# ArduinoNano7segSCH.net
KiCad netlist of a schematic drawn in Altium Designer
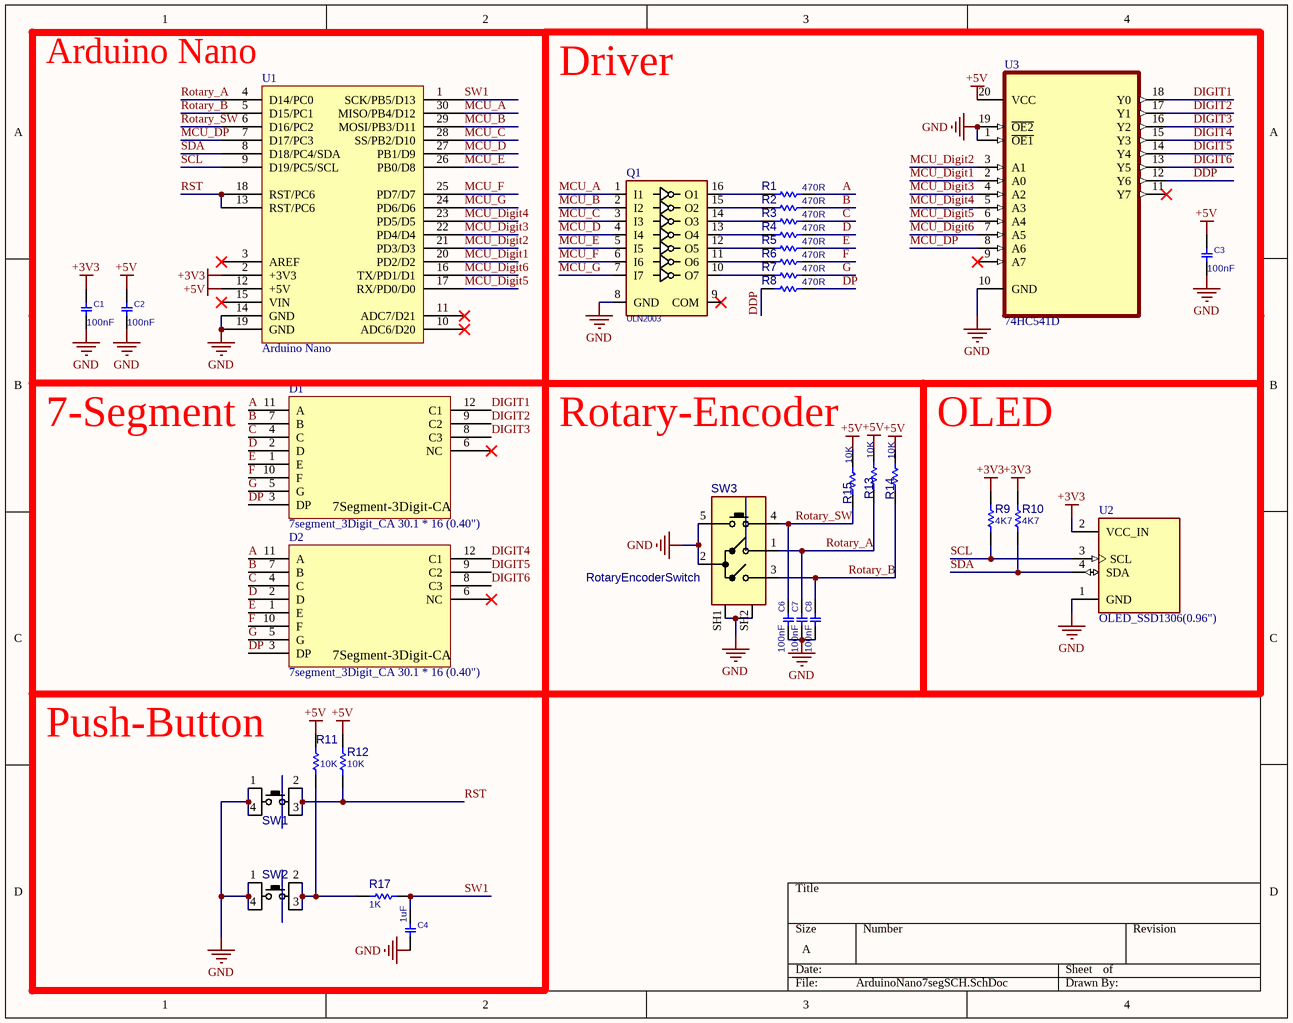
[diagram p0: ArduinoNano7segSCH.SchDoc]

(export (version "E")
  (design (tool "Eeschema 10.0.6"))
  (components
    (comp (ref "C1")
      (value "100nF")
      (footprint "C0805")
      (description "CAP, MLCC")
      (fields (field (name "MANF_P#") "MANF_PART#"))
      (libsource (lib "passive_smd") (part "CAP_SMD_MLCC_0805"))
    )
    (comp (ref "C2")
      (value "100nF")
      (footprint "C0805")
      (description "CAP, MLCC")
      (fields (field (name "MANF_P#") "MANF_PART#"))
      (libsource (lib "passive_smd") (part "CAP_SMD_MLCC_0805"))
    )
    (comp (ref "C3")
      (value "100nF")
      (footprint "C0805")
      (description "CAP, MLCC")
      (fields (field (name "MANF_P#") "MANF_PART#"))
      (libsource (lib "passive_smd") (part "CAP_SMD_MLCC_0805"))
    )
    (comp (ref "C4")
      (value "1uF")
      (footprint "C0805")
      (description "CAP, MLCC")
      (fields (field (name "MANF_P#") "MANF_PART#"))
      (libsource (lib "passive_smd") (part "CAP_SMD_MLCC_0805"))
    )
    (comp (ref "C6")
      (value "100nF")
      (footprint "C0805")
      (description "CAP, MLCC")
      (fields (field (name "MANF_P#") "MANF_PART#"))
      (libsource (lib "passive_smd") (part "CAP_SMD_MLCC_0805"))
    )
    (comp (ref "C7")
      (value "100nF")
      (footprint "C0805")
      (description "CAP, MLCC")
      (fields (field (name "MANF_P#") "MANF_PART#"))
      (libsource (lib "passive_smd") (part "CAP_SMD_MLCC_0805"))
    )
    (comp (ref "C8")
      (value "100nF")
      (footprint "C0805")
      (description "CAP, MLCC")
      (fields (field (name "MANF_P#") "MANF_PART#"))
      (libsource (lib "passive_smd") (part "CAP_SMD_MLCC_0805"))
    )
    (comp (ref "D1")
      (value "7segment_3Digit_CA 30.1 * 16 (0.40\")")
      (footprint "7Seg3Digit")
      (libsource (lib "Mehrdad") (part "7segment_3Digit_CA"))
    )
    (comp (ref "D2")
      (value "7segment_3Digit_CA 30.1 * 16 (0.40\")")
      (footprint "7Seg3Digit")
      (libsource (lib "Mehrdad") (part "7segment_3Digit_CA"))
    )
    (comp (ref "Q1")
      (value "ULN2003")
      (footprint "SO_16")
      (description "Darlington, 7-CH, 50V, 0.5A, 5V TTL/CMOS")
      (fields (field (name "MANF_P#") "ULN2003D1") (field (name "MANF") "ST"))
      (libsource (lib "transistor_bjt") (part "ULN2003_SOP16_ST"))
    )
    (comp (ref "R1")
      (value "470R")
      (footprint "R0805")
      (description "RESISTOR, SMD")
      (libsource (lib "passive_smd") (part "RES_SMD_0805"))
    )
    (comp (ref "R2")
      (value "470R")
      (footprint "R0805")
      (description "RESISTOR, SMD")
      (libsource (lib "passive_smd") (part "RES_SMD_0805"))
    )
    (comp (ref "R3")
      (value "470R")
      (footprint "R0805")
      (description "RESISTOR, SMD")
      (libsource (lib "passive_smd") (part "RES_SMD_0805"))
    )
    (comp (ref "R4")
      (value "470R")
      (footprint "R0805")
      (description "RESISTOR, SMD")
      (libsource (lib "passive_smd") (part "RES_SMD_0805"))
    )
    (comp (ref "R5")
      (value "470R")
      (footprint "R0805")
      (description "RESISTOR, SMD")
      (libsource (lib "passive_smd") (part "RES_SMD_0805"))
    )
    (comp (ref "R6")
      (value "470R")
      (footprint "R0805")
      (description "RESISTOR, SMD")
      (libsource (lib "passive_smd") (part "RES_SMD_0805"))
    )
    (comp (ref "R7")
      (value "470R")
      (footprint "R0805")
      (description "RESISTOR, SMD")
      (libsource (lib "passive_smd") (part "RES_SMD_0805"))
    )
    (comp (ref "R8")
      (value "470R")
      (footprint "R0805")
      (description "RESISTOR, SMD")
      (libsource (lib "passive_smd") (part "RES_SMD_0805"))
    )
    (comp (ref "R9")
      (value "4K7")
      (footprint "R0805")
      (description "RESISTOR, SMD")
      (libsource (lib "passive_smd") (part "RES_SMD_0805"))
    )
    (comp (ref "R10")
      (value "4K7")
      (footprint "R0805")
      (description "RESISTOR, SMD")
      (libsource (lib "passive_smd") (part "RES_SMD_0805"))
    )
    (comp (ref "R11")
      (value "10K")
      (footprint "R0805")
      (description "RESISTOR, SMD")
      (libsource (lib "passive_smd") (part "RES_SMD_0805"))
    )
    (comp (ref "R12")
      (value "10K")
      (footprint "R0805")
      (description "RESISTOR, SMD")
      (libsource (lib "passive_smd") (part "RES_SMD_0805"))
    )
    (comp (ref "R13")
      (value "10K")
      (footprint "R0805")
      (description "RESISTOR, SMD")
      (libsource (lib "passive_smd") (part "RES_SMD_0805"))
    )
    (comp (ref "R14")
      (value "10K")
      (footprint "R0805")
      (description "RESISTOR, SMD")
      (libsource (lib "passive_smd") (part "RES_SMD_0805"))
    )
    (comp (ref "R15")
      (value "10K")
      (footprint "R0805")
      (description "RESISTOR, SMD")
      (libsource (lib "passive_smd") (part "RES_SMD_0805"))
    )
    (comp (ref "R17")
      (value "1K")
      (footprint "R0805")
      (description "RESISTOR, SMD")
      (libsource (lib "passive_smd") (part "RES_SMD_0805"))
    )
    (comp (ref "SW1")
      (value "PUSHBUTTON")
      (footprint "SWPBS_SPDT_6X6X4")
      (description "SWITCH, PUSH BUTTON, TACTILE, SMD, SPDT, 6X6X4.3mm")
      (fields (field (name "MANF") "Bond-Tact") (field (name "MANF_P#") "TS-1143S"))
      (libsource (lib "switch_tact_PUSHB") (part "SWPBS_SPDT_6X6X4"))
    )
    (comp (ref "SW2")
      (value "PUSHBUTTON")
      (footprint "SWPBT_SPDT_12X12SKHC")
      (description "SWITCH, PUSH BUTTON, TACTILE, THD, SPDT, 12X12X7.3mm")
      (fields (field (name "MANF") "ALPS") (field (name "MANF_P#") "SKHCBEA010"))
      (libsource (lib "switch_tact_PUSHB") (part "SWPBT_SPDT_12X12_SKHCBEA010"))
    )
    (comp (ref "SW3")
      (value "RotaryEncoderSwitch")
      (footprint "SWROT_11MM")
      (description "SWITCH, ROTARY Encoder, 11mm Metal Shaft")
      (fields (field (name "MANF") "Alpha") (field (name "MANF_PART#") "RE111F-41B3N-15F-20P"))
      (libsource (lib "switch_rotary_encoder") (part "SWROT_11MM"))
    )
    (comp (ref "U1")
      (value "Arduino Nano")
      (footprint "Arduino Nano")
      (libsource (lib "Mehrdad") (part "Arduino Nano"))
    )
    (comp (ref "U2")
      (value "OLED_SSD1306(0.96\")")
      (footprint "OLED_Display 0.96\" 64*128")
      (libsource (lib "Mehrdad") (part "OLED_Display 0.96{dblquote} 64*128"))
    )
    (comp (ref "U3")
      (value "74HC541D")
      (footprint "74HC541D")
      (description "Buffer, Non-Inverting 1 Element 8 Bit per Element 3-State Output 20-SOIC")
      (libsource (lib "Mehrdad") (part "74HC541D"))
    )
  )
  (nets
    (net (code "1") (name "+3V3") (class "Default")
      (node (ref "C1") (pin "2") (pinfunction "2_2") (pintype "passive"))
      (node (ref "R10") (pin "2") (pinfunction "2_2") (pintype "passive"))
      (node (ref "R9") (pin "2") (pinfunction "2_2") (pintype "passive"))
      (node (ref "U1") (pin "2") (pinfunction "+3V3_2") (pintype "passive"))
      (node (ref "U2") (pin "2") (pinfunction "VCC_IN_2") (pintype "power_in"))
    )
    (net (code "2") (name "+5V") (class "Default")
      (node (ref "C2") (pin "2") (pinfunction "2_2") (pintype "passive"))
      (node (ref "C3") (pin "2") (pinfunction "2_2") (pintype "passive"))
      (node (ref "R11") (pin "2") (pinfunction "2_2") (pintype "passive"))
      (node (ref "R12") (pin "2") (pinfunction "2_2") (pintype "passive"))
      (node (ref "R13") (pin "2") (pinfunction "2_2") (pintype "passive"))
      (node (ref "R14") (pin "2") (pinfunction "2_2") (pintype "passive"))
      (node (ref "R15") (pin "2") (pinfunction "2_2") (pintype "passive"))
      (node (ref "U1") (pin "12") (pinfunction "+5V_12") (pintype "passive"))
      (node (ref "U3") (pin "20") (pinfunction "VCC_20") (pintype "power_in"))
    )
    (net (code "3") (name "/A") (class "Default")
      (node (ref "D1") (pin "11") (pinfunction "A_11") (pintype "passive"))
      (node (ref "D2") (pin "11") (pinfunction "A_11") (pintype "passive"))
      (node (ref "R1") (pin "1") (pinfunction "1_1") (pintype "passive"))
    )
    (net (code "4") (name "/B") (class "Default")
      (node (ref "D1") (pin "7") (pinfunction "B_7") (pintype "passive"))
      (node (ref "D2") (pin "7") (pinfunction "B_7") (pintype "passive"))
      (node (ref "R2") (pin "1") (pinfunction "1_1") (pintype "passive"))
    )
    (net (code "5") (name "/C") (class "Default")
      (node (ref "D1") (pin "4") (pinfunction "C_4") (pintype "passive"))
      (node (ref "D2") (pin "4") (pinfunction "C_4") (pintype "passive"))
      (node (ref "R3") (pin "1") (pinfunction "1_1") (pintype "passive"))
    )
    (net (code "6") (name "/D") (class "Default")
      (node (ref "D1") (pin "2") (pinfunction "D_2") (pintype "passive"))
      (node (ref "D2") (pin "2") (pinfunction "D_2") (pintype "passive"))
      (node (ref "R4") (pin "1") (pinfunction "1_1") (pintype "passive"))
    )
    (net (code "7") (name "/DDP") (class "Default")
      (node (ref "R8") (pin "2") (pinfunction "2_2") (pintype "passive"))
      (node (ref "U3") (pin "12") (pinfunction "Y6_12") (pintype "output"))
    )
    (net (code "8") (name "/DIGIT1") (class "Default")
      (node (ref "D1") (pin "12") (pinfunction "C1_12") (pintype "passive"))
      (node (ref "U3") (pin "18") (pinfunction "Y0_18") (pintype "output"))
    )
    (net (code "9") (name "/DIGIT2") (class "Default")
      (node (ref "D1") (pin "9") (pinfunction "C2_9") (pintype "passive"))
      (node (ref "U3") (pin "17") (pinfunction "Y1_17") (pintype "output"))
    )
    (net (code "10") (name "/DIGIT3") (class "Default")
      (node (ref "D1") (pin "8") (pinfunction "C3_8") (pintype "passive"))
      (node (ref "U3") (pin "16") (pinfunction "Y2_16") (pintype "output"))
    )
    (net (code "11") (name "/DIGIT4") (class "Default")
      (node (ref "D2") (pin "12") (pinfunction "C1_12") (pintype "passive"))
      (node (ref "U3") (pin "15") (pinfunction "Y3_15") (pintype "output"))
    )
    (net (code "12") (name "/DIGIT5") (class "Default")
      (node (ref "D2") (pin "9") (pinfunction "C2_9") (pintype "passive"))
      (node (ref "U3") (pin "14") (pinfunction "Y4_14") (pintype "output"))
    )
    (net (code "13") (name "/DIGIT6") (class "Default")
      (node (ref "D2") (pin "8") (pinfunction "C3_8") (pintype "passive"))
      (node (ref "U3") (pin "13") (pinfunction "Y5_13") (pintype "output"))
    )
    (net (code "14") (name "/DP") (class "Default")
      (node (ref "D1") (pin "3") (pinfunction "DP_3") (pintype "passive"))
      (node (ref "D2") (pin "3") (pinfunction "DP_3") (pintype "passive"))
      (node (ref "R8") (pin "1") (pinfunction "1_1") (pintype "passive"))
    )
    (net (code "15") (name "/E") (class "Default")
      (node (ref "D1") (pin "1") (pinfunction "E_1") (pintype "passive"))
      (node (ref "D2") (pin "1") (pinfunction "E_1") (pintype "passive"))
      (node (ref "R5") (pin "1") (pinfunction "1_1") (pintype "passive"))
    )
    (net (code "16") (name "/F") (class "Default")
      (node (ref "D1") (pin "10") (pinfunction "F_10") (pintype "passive"))
      (node (ref "D2") (pin "10") (pinfunction "F_10") (pintype "passive"))
      (node (ref "R6") (pin "1") (pinfunction "1_1") (pintype "passive"))
    )
    (net (code "17") (name "/G") (class "Default")
      (node (ref "D1") (pin "5") (pinfunction "G_5") (pintype "passive"))
      (node (ref "D2") (pin "5") (pinfunction "G_5") (pintype "passive"))
      (node (ref "R7") (pin "1") (pinfunction "1_1") (pintype "passive"))
    )
    (net (code "18") (name "/MCU_A") (class "Default")
      (node (ref "Q1") (pin "1") (pinfunction "I1_1") (pintype "passive"))
      (node (ref "U1") (pin "30") (pinfunction "MISO/PB4/D12_30") (pintype "passive"))
    )
    (net (code "19") (name "/MCU_B") (class "Default")
      (node (ref "Q1") (pin "2") (pinfunction "I2_2") (pintype "passive"))
      (node (ref "U1") (pin "29") (pinfunction "MOSI/PB3/D11_29") (pintype "passive"))
    )
    (net (code "20") (name "/MCU_C") (class "Default")
      (node (ref "Q1") (pin "3") (pinfunction "I3_3") (pintype "passive"))
      (node (ref "U1") (pin "28") (pinfunction "SS/PB2/D10_28") (pintype "passive"))
    )
    (net (code "21") (name "/MCU_D") (class "Default")
      (node (ref "Q1") (pin "4") (pinfunction "I4_4") (pintype "passive"))
      (node (ref "U1") (pin "27") (pinfunction "PB1/D9_27") (pintype "passive"))
    )
    (net (code "22") (name "/MCU_DP") (class "Default")
      (node (ref "U1") (pin "7") (pinfunction "D17/PC3_7") (pintype "passive"))
      (node (ref "U3") (pin "8") (pinfunction "A6_8") (pintype "input"))
    )
    (net (code "23") (name "/MCU_Digit1") (class "Default")
      (node (ref "U1") (pin "20") (pinfunction "PD2/D2_20") (pintype "passive"))
      (node (ref "U3") (pin "2") (pinfunction "A0_2") (pintype "input"))
    )
    (net (code "24") (name "/MCU_Digit2") (class "Default")
      (node (ref "U1") (pin "21") (pinfunction "PD3/D3_21") (pintype "passive"))
      (node (ref "U3") (pin "3") (pinfunction "A1_3") (pintype "input"))
    )
    (net (code "25") (name "/MCU_Digit3") (class "Default")
      (node (ref "U1") (pin "22") (pinfunction "PD4/D4_22") (pintype "passive"))
      (node (ref "U3") (pin "4") (pinfunction "A2_4") (pintype "input"))
    )
    (net (code "26") (name "/MCU_Digit4") (class "Default")
      (node (ref "U1") (pin "23") (pinfunction "PD5/D5_23") (pintype "passive"))
      (node (ref "U3") (pin "5") (pinfunction "A3_5") (pintype "input"))
    )
    (net (code "27") (name "/MCU_Digit5") (class "Default")
      (node (ref "U1") (pin "17") (pinfunction "RX/PD0/D0_17") (pintype "passive"))
      (node (ref "U3") (pin "6") (pinfunction "A4_6") (pintype "input"))
    )
    (net (code "28") (name "/MCU_Digit6") (class "Default")
      (node (ref "U1") (pin "16") (pinfunction "TX/PD1/D1_16") (pintype "passive"))
      (node (ref "U3") (pin "7") (pinfunction "A5_7") (pintype "input"))
    )
    (net (code "29") (name "/MCU_E") (class "Default")
      (node (ref "Q1") (pin "5") (pinfunction "I5_5") (pintype "passive"))
      (node (ref "U1") (pin "26") (pinfunction "PB0/D8_26") (pintype "passive"))
    )
    (net (code "30") (name "/MCU_F") (class "Default")
      (node (ref "Q1") (pin "6") (pinfunction "I6_6") (pintype "passive"))
      (node (ref "U1") (pin "25") (pinfunction "PD7/D7_25") (pintype "passive"))
    )
    (net (code "31") (name "/MCU_G") (class "Default")
      (node (ref "Q1") (pin "7") (pinfunction "I7_7") (pintype "passive"))
      (node (ref "U1") (pin "24") (pinfunction "PD6/D6_24") (pintype "passive"))
    )
    (net (code "32") (name "/RST") (class "Default")
      (node (ref "R12") (pin "1") (pinfunction "1_1") (pintype "passive"))
      (node (ref "SW1") (pin "2") (pinfunction "P3_2") (pintype "passive"))
      (node (ref "SW1") (pin "3") (pinfunction "P4_3") (pintype "passive"))
      (node (ref "U1") (pin "13") (pinfunction "RST/PC6_13") (pintype "passive"))
      (node (ref "U1") (pin "18") (pinfunction "RST/PC6_18") (pintype "passive"))
    )
    (net (code "33") (name "/Rotary_A") (class "Default")
      (node (ref "C7") (pin "2") (pinfunction "2_2") (pintype "passive"))
      (node (ref "R13") (pin "1") (pinfunction "1_1") (pintype "passive"))
      (node (ref "SW3") (pin "1") (pinfunction "A_1") (pintype "passive"))
      (node (ref "U1") (pin "4") (pinfunction "D14/PC0_4") (pintype "passive"))
    )
    (net (code "34") (name "/Rotary_B") (class "Default")
      (node (ref "C8") (pin "2") (pinfunction "2_2") (pintype "passive"))
      (node (ref "R14") (pin "1") (pinfunction "1_1") (pintype "passive"))
      (node (ref "SW3") (pin "3") (pinfunction "B_3") (pintype "passive"))
      (node (ref "U1") (pin "5") (pinfunction "D15/PC1_5") (pintype "passive"))
    )
    (net (code "35") (name "/Rotary_SW") (class "Default")
      (node (ref "C6") (pin "2") (pinfunction "2_2") (pintype "passive"))
      (node (ref "R15") (pin "1") (pinfunction "1_1") (pintype "passive"))
      (node (ref "SW3") (pin "4") (pinfunction "E_4") (pintype "passive"))
      (node (ref "U1") (pin "6") (pinfunction "D16/PC2_6") (pintype "passive"))
    )
    (net (code "36") (name "/SCL") (class "Default")
      (node (ref "R9") (pin "1") (pinfunction "1_1") (pintype "passive"))
      (node (ref "U1") (pin "9") (pinfunction "D19/PC5/SCL_9") (pintype "passive"))
      (node (ref "U2") (pin "3") (pinfunction "SCL_3") (pintype "input"))
    )
    (net (code "37") (name "/SDA") (class "Default")
      (node (ref "R10") (pin "1") (pinfunction "1_1") (pintype "passive"))
      (node (ref "U1") (pin "8") (pinfunction "D18/PC4/SDA_8") (pintype "passive"))
      (node (ref "U2") (pin "4") (pinfunction "SDA_4") (pintype "bidirectional"))
    )
    (net (code "38") (name "/SW1") (class "Default")
      (node (ref "C4") (pin "2") (pinfunction "2_2") (pintype "passive"))
      (node (ref "R17") (pin "1") (pinfunction "1_1") (pintype "passive"))
      (node (ref "U1") (pin "1") (pinfunction "SCK/PB5/D13_1") (pintype "passive"))
    )
    (net (code "39") (name "GND") (class "Default")
      (node (ref "C1") (pin "1") (pinfunction "1_1") (pintype "passive"))
      (node (ref "C2") (pin "1") (pinfunction "1_1") (pintype "passive"))
      (node (ref "C3") (pin "1") (pinfunction "1_1") (pintype "passive"))
      (node (ref "C4") (pin "1") (pinfunction "1_1") (pintype "passive"))
      (node (ref "C6") (pin "1") (pinfunction "1_1") (pintype "passive"))
      (node (ref "C7") (pin "1") (pinfunction "1_1") (pintype "passive"))
      (node (ref "C8") (pin "1") (pinfunction "1_1") (pintype "passive"))
      (node (ref "Q1") (pin "8") (pinfunction "GND_8") (pintype "passive"))
      (node (ref "SW1") (pin "1") (pinfunction "P1_1") (pintype "passive"))
      (node (ref "SW1") (pin "4") (pinfunction "P2_4") (pintype "passive"))
      (node (ref "SW2") (pin "1") (pinfunction "P1_1") (pintype "passive"))
      (node (ref "SW2") (pin "4") (pinfunction "P2_4") (pintype "passive"))
      (node (ref "SW3") (pin "2") (pinfunction "C_2") (pintype "passive"))
      (node (ref "SW3") (pin "5") (pinfunction "D_5") (pintype "passive"))
      (node (ref "SW3") (pin "SH1") (pinfunction "SH1_SH1") (pintype "passive"))
      (node (ref "SW3") (pin "SH2") (pinfunction "SH2_SH2") (pintype "passive"))
      (node (ref "U1") (pin "14") (pinfunction "GND_14") (pintype "passive"))
      (node (ref "U1") (pin "19") (pinfunction "GND_19") (pintype "passive"))
      (node (ref "U2") (pin "1") (pinfunction "GND_1") (pintype "power_in"))
      (node (ref "U3") (pin "1") (pinfunction "~{OE1}_1") (pintype "input"))
      (node (ref "U3") (pin "10") (pinfunction "GND_10") (pintype "passive"))
      (node (ref "U3") (pin "19") (pinfunction "~{OE2}_19") (pintype "input"))
    )
    (net (code "40") (name "Net-(Q1-O1)") (class "Default")
      (node (ref "Q1") (pin "16") (pinfunction "O1_16") (pintype "passive"))
      (node (ref "R1") (pin "2") (pinfunction "2_2") (pintype "passive"))
    )
    (net (code "41") (name "Net-(Q1-O2)") (class "Default")
      (node (ref "Q1") (pin "15") (pinfunction "O2_15") (pintype "passive"))
      (node (ref "R2") (pin "2") (pinfunction "2_2") (pintype "passive"))
    )
    (net (code "42") (name "Net-(Q1-O3)") (class "Default")
      (node (ref "Q1") (pin "14") (pinfunction "O3_14") (pintype "passive"))
      (node (ref "R3") (pin "2") (pinfunction "2_2") (pintype "passive"))
    )
    (net (code "43") (name "Net-(Q1-O4)") (class "Default")
      (node (ref "Q1") (pin "13") (pinfunction "O4_13") (pintype "passive"))
      (node (ref "R4") (pin "2") (pinfunction "2_2") (pintype "passive"))
    )
    (net (code "44") (name "Net-(Q1-O5)") (class "Default")
      (node (ref "Q1") (pin "12") (pinfunction "O5_12") (pintype "passive"))
      (node (ref "R5") (pin "2") (pinfunction "2_2") (pintype "passive"))
    )
    (net (code "45") (name "Net-(Q1-O6)") (class "Default")
      (node (ref "Q1") (pin "11") (pinfunction "O6_11") (pintype "passive"))
      (node (ref "R6") (pin "2") (pinfunction "2_2") (pintype "passive"))
    )
    (net (code "46") (name "Net-(Q1-O7)") (class "Default")
      (node (ref "Q1") (pin "10") (pinfunction "O7_10") (pintype "passive"))
      (node (ref "R7") (pin "2") (pinfunction "2_2") (pintype "passive"))
    )
    (net (code "47") (name "Net-(SW2-P3)") (class "Default")
      (node (ref "R11") (pin "1") (pinfunction "1_1") (pintype "passive"))
      (node (ref "R17") (pin "2") (pinfunction "2_2") (pintype "passive"))
      (node (ref "SW2") (pin "2") (pinfunction "P3_2") (pintype "passive"))
      (node (ref "SW2") (pin "3") (pinfunction "P4_3") (pintype "passive"))
    )
    (net (code "48") (name "unconnected-(D1-NC-Pad6)") (class "Default")
      (node (ref "D1") (pin "6") (pinfunction "NC_6") (pintype "passive+no_connect"))
    )
    (net (code "49") (name "unconnected-(D2-NC-Pad6)") (class "Default")
      (node (ref "D2") (pin "6") (pinfunction "NC_6") (pintype "passive+no_connect"))
    )
    (net (code "50") (name "unconnected-(Q1-COM-Pad9)") (class "Default")
      (node (ref "Q1") (pin "9") (pinfunction "COM_9") (pintype "passive+no_connect"))
    )
    (net (code "51") (name "unconnected-(U1-ADC6{slash}D20-Pad10)") (class "Default")
      (node (ref "U1") (pin "10") (pinfunction "ADC6/D20_10") (pintype "passive+no_connect"))
    )
    (net (code "52") (name "unconnected-(U1-ADC7{slash}D21-Pad11)") (class "Default")
      (node (ref "U1") (pin "11") (pinfunction "ADC7/D21_11") (pintype "passive+no_connect"))
    )
    (net (code "53") (name "unconnected-(U1-AREF-Pad3)") (class "Default")
      (node (ref "U1") (pin "3") (pinfunction "AREF_3") (pintype "passive+no_connect"))
    )
    (net (code "54") (name "unconnected-(U1-VIN-Pad15)") (class "Default")
      (node (ref "U1") (pin "15") (pinfunction "VIN_15") (pintype "passive+no_connect"))
    )
    (net (code "55") (name "unconnected-(U3-A7-Pad9)") (class "Default")
      (node (ref "U3") (pin "9") (pinfunction "A7_9") (pintype "input+no_connect"))
    )
    (net (code "56") (name "unconnected-(U3-Y7-Pad11)") (class "Default")
      (node (ref "U3") (pin "11") (pinfunction "Y7_11") (pintype "output+no_connect"))
    )
  )
)
